# STM32.net
KiCad netlist of a schematic drawn in Altium Designer
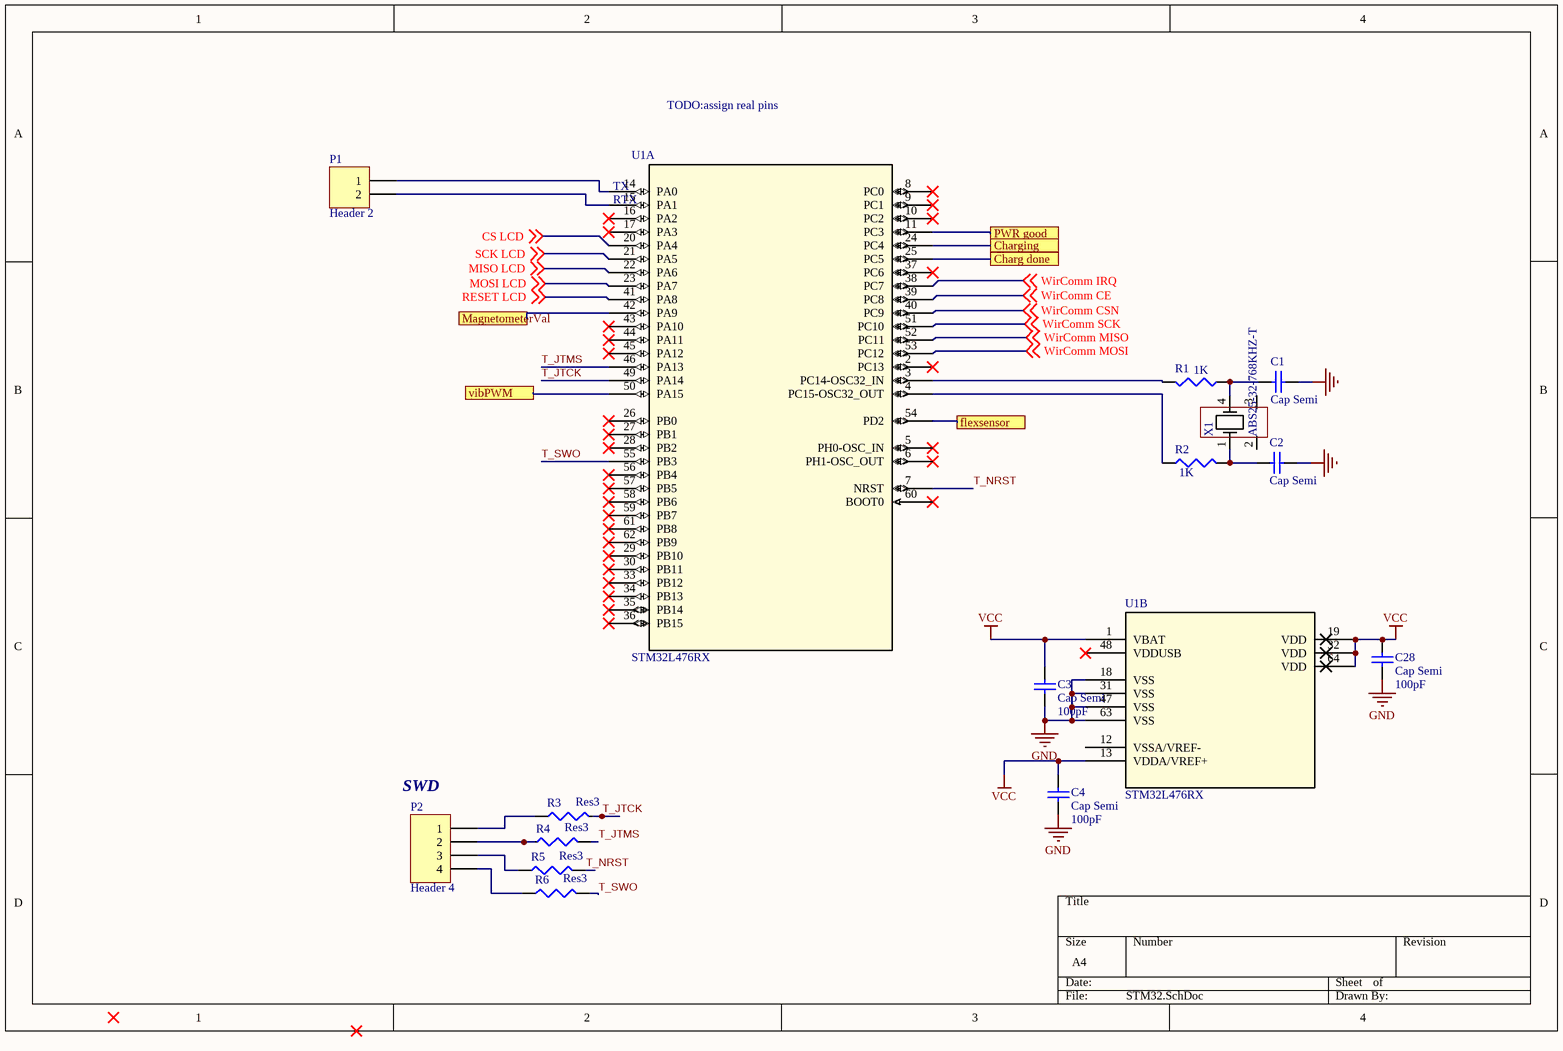
[diagram p0: STM32.SchDoc]

(export (version "E")
  (design (tool "Eeschema 10.0.6"))
  (components
    (comp (ref "C1")
      (value "Cap Semi")
      (footprint "C1206")
      (description "Capacitor (Semiconductor SIM Model)")
      (fields (field (name "PUBLISHER") "Altium Limited"))
      (libsource (lib "Miscellaneous Devices") (part "Cap Semi"))
    )
    (comp (ref "C2")
      (value "Cap Semi")
      (footprint "C1206")
      (description "Capacitor (Semiconductor SIM Model)")
      (fields (field (name "PUBLISHER") "Altium Limited"))
      (libsource (lib "Miscellaneous Devices") (part "Cap Semi"))
    )
    (comp (ref "C3")
      (value "Cap Semi")
      (footprint "C1206")
      (description "Capacitor (Semiconductor SIM Model)")
      (fields (field (name "ALTIUM_VALUE") "100pF") (field (name "PUBLISHER") "Altium Limited"))
      (libsource (lib "Miscellaneous Devices") (part "Cap Semi"))
    )
    (comp (ref "C4")
      (value "Cap Semi")
      (footprint "C1206")
      (description "Capacitor (Semiconductor SIM Model)")
      (fields (field (name "ALTIUM_VALUE") "100pF") (field (name "PUBLISHER") "Altium Limited"))
      (libsource (lib "Miscellaneous Devices") (part "Cap Semi"))
    )
    (comp (ref "C28")
      (value "Cap Semi")
      (footprint "C1206")
      (description "Capacitor (Semiconductor SIM Model)")
      (fields (field (name "ALTIUM_VALUE") "100pF") (field (name "PUBLISHER") "Altium Limited"))
      (libsource (lib "Miscellaneous Devices") (part "Cap Semi"))
    )
    (comp (ref "P1")
      (value "Header 2")
      (footprint "HDR1X2")
      (description "Header, 2-Pin")
      (fields (field (name "PUBLISHER") "Altium Limited"))
      (libsource (lib "Miscellaneous Connectors") (part "Header 2"))
    )
    (comp (ref "P2")
      (value "Header 4")
      (footprint "HDR1X4")
      (description "Header, 4-Pin")
      (fields (field (name "PUBLISHER") "Altium Limited"))
      (libsource (lib "Miscellaneous Connectors") (part "Header 4"))
    )
    (comp (ref "R1")
      (value "1K")
      (footprint "J1-0603")
      (description "Resistor")
      (fields (field (name "Comment") "Res3") (field (name "PUBLISHER") "Altium Limited"))
      (libsource (lib "Miscellaneous Devices") (part "Res3"))
    )
    (comp (ref "R2")
      (value "1K")
      (footprint "J1-0603")
      (description "Resistor")
      (fields (field (name "Comment") "Res3") (field (name "PUBLISHER") "Altium Limited"))
      (libsource (lib "Miscellaneous Devices") (part "Res3"))
    )
    (comp (ref "R3")
      (value "Res3")
      (footprint "J1-0603")
      (description "Resistor")
      (fields (field (name "PUBLISHER") "Altium Limited"))
      (libsource (lib "Miscellaneous Devices") (part "Res3"))
    )
    (comp (ref "R4")
      (value "Res3")
      (footprint "J1-0603")
      (description "Resistor")
      (fields (field (name "PUBLISHER") "Altium Limited"))
      (libsource (lib "Miscellaneous Devices") (part "Res3"))
    )
    (comp (ref "R5")
      (value "Res3")
      (footprint "J1-0603")
      (description "Resistor")
      (fields (field (name "PUBLISHER") "Altium Limited"))
      (libsource (lib "Miscellaneous Devices") (part "Res3"))
    )
    (comp (ref "R6")
      (value "Res3")
      (footprint "J1-0603")
      (description "Resistor")
      (fields (field (name "PUBLISHER") "Altium Limited"))
      (libsource (lib "Miscellaneous Devices") (part "Res3"))
    )
    (comp (ref "U1")
      (value "STM32L476RX")
      (footprint "LQFP64-10x10mm")
      (description "Imported")
      (fields
        (field (name "MANUFACTURER_PART_NUMBER") "stm32l476rx")
        (field (name "COPYRIGHT") "Copyright (C) 2016 Accelerated Designs. All rights reserved")
      )
      (libsource (lib "MainBoard") (part "STM32L476RX"))
    )
    (comp (ref "X1")
      (value "ABS25-32-768KHZ-T")
      (footprint "XTAL_ABS25-32-768KHZ-T")
      (fields (field (name "MF") "Abracon"))
      (libsource (lib "HGCDLibrary") (part "ABS25-32-768KHZ-T"))
    )
  )
  (nets
    (net (code "1") (name "/Charg done") (class "Default")
      (node (ref "U1") (pin "25") (pinfunction "PC5_25") (pintype "bidirectional"))
    )
    (net (code "2") (name "/Charging") (class "Default")
      (node (ref "U1") (pin "24") (pinfunction "PC4_24") (pintype "bidirectional"))
    )
    (net (code "3") (name "/MagnetometerVal") (class "Default")
      (node (ref "U1") (pin "42") (pinfunction "PA9_42") (pintype "bidirectional"))
    )
    (net (code "4") (name "/PWR good") (class "Default")
      (node (ref "U1") (pin "11") (pinfunction "PC3_11") (pintype "bidirectional"))
    )
    (net (code "5") (name "/T_JTCK") (class "Default")
      (node (ref "R3") (pin "2") (pinfunction "2_2") (pintype "passive"))
      (node (ref "U1") (pin "49") (pinfunction "PA14_49") (pintype "bidirectional"))
    )
    (net (code "6") (name "/T_JTMS") (class "Default")
      (node (ref "R4") (pin "2") (pinfunction "2_2") (pintype "passive"))
      (node (ref "U1") (pin "46") (pinfunction "PA13_46") (pintype "bidirectional"))
    )
    (net (code "7") (name "/T_NRST") (class "Default")
      (node (ref "R5") (pin "2") (pinfunction "2_2") (pintype "passive"))
      (node (ref "U1") (pin "7") (pinfunction "NRST_7") (pintype "bidirectional"))
    )
    (net (code "8") (name "/T_SWO") (class "Default")
      (node (ref "R6") (pin "2") (pinfunction "2_2") (pintype "passive"))
      (node (ref "U1") (pin "55") (pinfunction "PB3_55") (pintype "bidirectional"))
    )
    (net (code "9") (name "/flexsensor") (class "Default")
      (node (ref "U1") (pin "54") (pinfunction "PD2_54") (pintype "bidirectional"))
    )
    (net (code "10") (name "/vibPWM") (class "Default")
      (node (ref "U1") (pin "50") (pinfunction "PA15_50") (pintype "bidirectional"))
    )
    (net (code "11") (name "CS LCD") (class "Default")
      (node (ref "U1") (pin "20") (pinfunction "PA4_20") (pintype "bidirectional"))
    )
    (net (code "12") (name "GND") (class "Default")
      (node (ref "C1") (pin "1") (pinfunction "1_1") (pintype "passive"))
      (node (ref "C2") (pin "1") (pinfunction "1_1") (pintype "passive"))
      (node (ref "C28") (pin "1") (pinfunction "1_1") (pintype "passive"))
      (node (ref "C3") (pin "1") (pinfunction "1_1") (pintype "passive"))
      (node (ref "C4") (pin "1") (pinfunction "1_1") (pintype "passive"))
      (node (ref "U1") (pin "18") (pinfunction "VSS_18") (pintype "power_in"))
      (node (ref "U1") (pin "31") (pinfunction "VSS_31") (pintype "power_in"))
      (node (ref "U1") (pin "47") (pinfunction "VSS_47") (pintype "power_in"))
      (node (ref "U1") (pin "63") (pinfunction "VSS_63") (pintype "power_in"))
    )
    (net (code "13") (name "MISO LCD") (class "Default")
      (node (ref "U1") (pin "22") (pinfunction "PA6_22") (pintype "bidirectional"))
    )
    (net (code "14") (name "MOSI LCD") (class "Default")
      (node (ref "U1") (pin "23") (pinfunction "PA7_23") (pintype "bidirectional"))
    )
    (net (code "15") (name "Net-(C1-Pad2)") (class "Default")
      (node (ref "C1") (pin "2") (pinfunction "2_2") (pintype "passive"))
      (node (ref "R1") (pin "2") (pinfunction "2_2") (pintype "passive"))
      (node (ref "X1") (pin "4") (pinfunction "4_4") (pintype "passive"))
    )
    (net (code "16") (name "Net-(C2-Pad2)") (class "Default")
      (node (ref "C2") (pin "2") (pinfunction "2_2") (pintype "passive"))
      (node (ref "R2") (pin "2") (pinfunction "2_2") (pintype "passive"))
      (node (ref "X1") (pin "1") (pinfunction "1_1") (pintype "passive"))
    )
    (net (code "17") (name "Net-(P2-Pad1)") (class "Default")
      (node (ref "P2") (pin "1") (pinfunction "1_1") (pintype "passive"))
      (node (ref "R3") (pin "1") (pinfunction "1_1") (pintype "passive"))
    )
    (net (code "18") (name "Net-(P2-Pad2)") (class "Default")
      (node (ref "P2") (pin "2") (pinfunction "2_2") (pintype "passive"))
      (node (ref "R4") (pin "1") (pinfunction "1_1") (pintype "passive"))
    )
    (net (code "19") (name "Net-(P2-Pad3)") (class "Default")
      (node (ref "P2") (pin "3") (pinfunction "3_3") (pintype "passive"))
      (node (ref "R5") (pin "1") (pinfunction "1_1") (pintype "passive"))
    )
    (net (code "20") (name "Net-(P2-Pad4)") (class "Default")
      (node (ref "P2") (pin "4") (pinfunction "4_4") (pintype "passive"))
      (node (ref "R6") (pin "1") (pinfunction "1_1") (pintype "passive"))
    )
    (net (code "21") (name "Net-(U1A-PA0)") (class "Default")
      (node (ref "P1") (pin "1") (pinfunction "1_1") (pintype "passive"))
      (node (ref "U1") (pin "14") (pinfunction "PA0_14") (pintype "bidirectional"))
    )
    (net (code "22") (name "Net-(U1A-PA1)") (class "Default")
      (node (ref "P1") (pin "2") (pinfunction "2_2") (pintype "passive"))
      (node (ref "U1") (pin "15") (pinfunction "PA1_15") (pintype "bidirectional"))
    )
    (net (code "23") (name "Net-(U1A-PC14-OSC32_IN)") (class "Default")
      (node (ref "R1") (pin "1") (pinfunction "1_1") (pintype "passive"))
      (node (ref "U1") (pin "3") (pinfunction "PC14-OSC32_IN_3") (pintype "bidirectional"))
    )
    (net (code "24") (name "Net-(U1A-PC15-OSC32_OUT)") (class "Default")
      (node (ref "R2") (pin "1") (pinfunction "1_1") (pintype "passive"))
      (node (ref "U1") (pin "4") (pinfunction "PC15-OSC32_OUT_4") (pintype "bidirectional"))
    )
    (net (code "25") (name "RESET LCD") (class "Default")
      (node (ref "U1") (pin "41") (pinfunction "PA8_41") (pintype "bidirectional"))
    )
    (net (code "26") (name "SCK LCD") (class "Default")
      (node (ref "U1") (pin "21") (pinfunction "PA5_21") (pintype "bidirectional"))
    )
    (net (code "27") (name "VCC") (class "Default")
      (node (ref "C28") (pin "2") (pinfunction "2_2") (pintype "passive"))
      (node (ref "C3") (pin "2") (pinfunction "2_2") (pintype "passive"))
      (node (ref "C4") (pin "2") (pinfunction "2_2") (pintype "passive"))
      (node (ref "U1") (pin "1") (pinfunction "VBAT_1") (pintype "power_in"))
      (node (ref "U1") (pin "13") (pinfunction "VDDA/VREF+_13") (pintype "power_in"))
      (node (ref "U1") (pin "19") (pinfunction "VDD_19") (pintype "power_in"))
      (node (ref "U1") (pin "32") (pinfunction "VDD_32") (pintype "power_in"))
      (node (ref "U1") (pin "64") (pinfunction "VDD_64") (pintype "power_in"))
    )
    (net (code "28") (name "WirComm CE") (class "Default")
      (node (ref "U1") (pin "39") (pinfunction "PC8_39") (pintype "bidirectional"))
    )
    (net (code "29") (name "WirComm CSN") (class "Default")
      (node (ref "U1") (pin "40") (pinfunction "PC9_40") (pintype "bidirectional"))
    )
    (net (code "30") (name "WirComm IRQ") (class "Default")
      (node (ref "U1") (pin "38") (pinfunction "PC7_38") (pintype "bidirectional"))
    )
    (net (code "31") (name "WirComm MISO") (class "Default")
      (node (ref "U1") (pin "52") (pinfunction "PC11_52") (pintype "bidirectional"))
    )
    (net (code "32") (name "WirComm MOSI") (class "Default")
      (node (ref "U1") (pin "53") (pinfunction "PC12_53") (pintype "bidirectional"))
    )
    (net (code "33") (name "WirComm SCK") (class "Default")
      (node (ref "U1") (pin "51") (pinfunction "PC10_51") (pintype "bidirectional"))
    )
    (net (code "34") (name "unconnected-(U1A-BOOT0-Pad60)") (class "Default")
      (node (ref "U1") (pin "60") (pinfunction "BOOT0_60") (pintype "input+no_connect"))
    )
    (net (code "35") (name "unconnected-(U1A-PA2-Pad16)") (class "Default")
      (node (ref "U1") (pin "16") (pinfunction "PA2_16") (pintype "bidirectional+no_connect"))
    )
    (net (code "36") (name "unconnected-(U1A-PA3-Pad17)") (class "Default")
      (node (ref "U1") (pin "17") (pinfunction "PA3_17") (pintype "bidirectional+no_connect"))
    )
    (net (code "37") (name "unconnected-(U1A-PA10-Pad43)") (class "Default")
      (node (ref "U1") (pin "43") (pinfunction "PA10_43") (pintype "bidirectional+no_connect"))
    )
    (net (code "38") (name "unconnected-(U1A-PA11-Pad44)") (class "Default")
      (node (ref "U1") (pin "44") (pinfunction "PA11_44") (pintype "bidirectional+no_connect"))
    )
    (net (code "39") (name "unconnected-(U1A-PA12-Pad45)") (class "Default")
      (node (ref "U1") (pin "45") (pinfunction "PA12_45") (pintype "bidirectional+no_connect"))
    )
    (net (code "40") (name "unconnected-(U1A-PB0-Pad26)") (class "Default")
      (node (ref "U1") (pin "26") (pinfunction "PB0_26") (pintype "bidirectional+no_connect"))
    )
    (net (code "41") (name "unconnected-(U1A-PB1-Pad27)") (class "Default")
      (node (ref "U1") (pin "27") (pinfunction "PB1_27") (pintype "bidirectional+no_connect"))
    )
    (net (code "42") (name "unconnected-(U1A-PB2-Pad28)") (class "Default")
      (node (ref "U1") (pin "28") (pinfunction "PB2_28") (pintype "bidirectional+no_connect"))
    )
    (net (code "43") (name "unconnected-(U1A-PB4-Pad56)") (class "Default")
      (node (ref "U1") (pin "56") (pinfunction "PB4_56") (pintype "bidirectional+no_connect"))
    )
    (net (code "44") (name "unconnected-(U1A-PB5-Pad57)") (class "Default")
      (node (ref "U1") (pin "57") (pinfunction "PB5_57") (pintype "bidirectional+no_connect"))
    )
    (net (code "45") (name "unconnected-(U1A-PB6-Pad58)") (class "Default")
      (node (ref "U1") (pin "58") (pinfunction "PB6_58") (pintype "bidirectional+no_connect"))
    )
    (net (code "46") (name "unconnected-(U1A-PB7-Pad59)") (class "Default")
      (node (ref "U1") (pin "59") (pinfunction "PB7_59") (pintype "bidirectional+no_connect"))
    )
    (net (code "47") (name "unconnected-(U1A-PB8-Pad61)") (class "Default")
      (node (ref "U1") (pin "61") (pinfunction "PB8_61") (pintype "bidirectional+no_connect"))
    )
    (net (code "48") (name "unconnected-(U1A-PB9-Pad62)") (class "Default")
      (node (ref "U1") (pin "62") (pinfunction "PB9_62") (pintype "bidirectional+no_connect"))
    )
    (net (code "49") (name "unconnected-(U1A-PB10-Pad29)") (class "Default")
      (node (ref "U1") (pin "29") (pinfunction "PB10_29") (pintype "bidirectional+no_connect"))
    )
    (net (code "50") (name "unconnected-(U1A-PB11-Pad30)") (class "Default")
      (node (ref "U1") (pin "30") (pinfunction "PB11_30") (pintype "bidirectional+no_connect"))
    )
    (net (code "51") (name "unconnected-(U1A-PB12-Pad33)") (class "Default")
      (node (ref "U1") (pin "33") (pinfunction "PB12_33") (pintype "bidirectional+no_connect"))
    )
    (net (code "52") (name "unconnected-(U1A-PB13-Pad34)") (class "Default")
      (node (ref "U1") (pin "34") (pinfunction "PB13_34") (pintype "bidirectional+no_connect"))
    )
    (net (code "53") (name "unconnected-(U1A-PB14-Pad35)") (class "Default")
      (node (ref "U1") (pin "35") (pinfunction "PB14_35") (pintype "bidirectional+no_connect"))
    )
    (net (code "54") (name "unconnected-(U1A-PB15-Pad36)") (class "Default")
      (node (ref "U1") (pin "36") (pinfunction "PB15_36") (pintype "bidirectional+no_connect"))
    )
    (net (code "55") (name "unconnected-(U1A-PC0-Pad8)") (class "Default")
      (node (ref "U1") (pin "8") (pinfunction "PC0_8") (pintype "bidirectional+no_connect"))
    )
    (net (code "56") (name "unconnected-(U1A-PC1-Pad9)") (class "Default")
      (node (ref "U1") (pin "9") (pinfunction "PC1_9") (pintype "bidirectional+no_connect"))
    )
    (net (code "57") (name "unconnected-(U1A-PC2-Pad10)") (class "Default")
      (node (ref "U1") (pin "10") (pinfunction "PC2_10") (pintype "bidirectional+no_connect"))
    )
    (net (code "58") (name "unconnected-(U1A-PC6-Pad37)") (class "Default")
      (node (ref "U1") (pin "37") (pinfunction "PC6_37") (pintype "bidirectional+no_connect"))
    )
    (net (code "59") (name "unconnected-(U1A-PC13-Pad2)") (class "Default")
      (node (ref "U1") (pin "2") (pinfunction "PC13_2") (pintype "bidirectional+no_connect"))
    )
    (net (code "60") (name "unconnected-(U1A-PH0-OSC_IN-Pad5)") (class "Default")
      (node (ref "U1") (pin "5") (pinfunction "PH0-OSC_IN_5") (pintype "bidirectional+no_connect"))
    )
    (net (code "61") (name "unconnected-(U1A-PH1-OSC_OUT-Pad6)") (class "Default")
      (node (ref "U1") (pin "6") (pinfunction "PH1-OSC_OUT_6") (pintype "bidirectional+no_connect"))
    )
    (net (code "62") (name "unconnected-(U1B-VDDUSB-Pad48)") (class "Default")
      (node (ref "U1") (pin "48") (pinfunction "VDDUSB_48") (pintype "power_in+no_connect"))
    )
    (net (code "63") (name "unconnected-(U1B-VSSA{slash}VREF--Pad12)") (class "Default")
      (node (ref "U1") (pin "12") (pinfunction "VSSA/VREF-_12") (pintype "power_in"))
    )
    (net (code "64") (name "unconnected-(X1-Pad2)") (class "Default")
      (node (ref "X1") (pin "2") (pinfunction "2_2") (pintype "passive"))
    )
    (net (code "65") (name "unconnected-(X1-Pad3)") (class "Default")
      (node (ref "X1") (pin "3") (pinfunction "3_3") (pintype "passive"))
    )
  )
)
